# led_driver.net
KiCad netlist of a schematic drawn in EAGLE
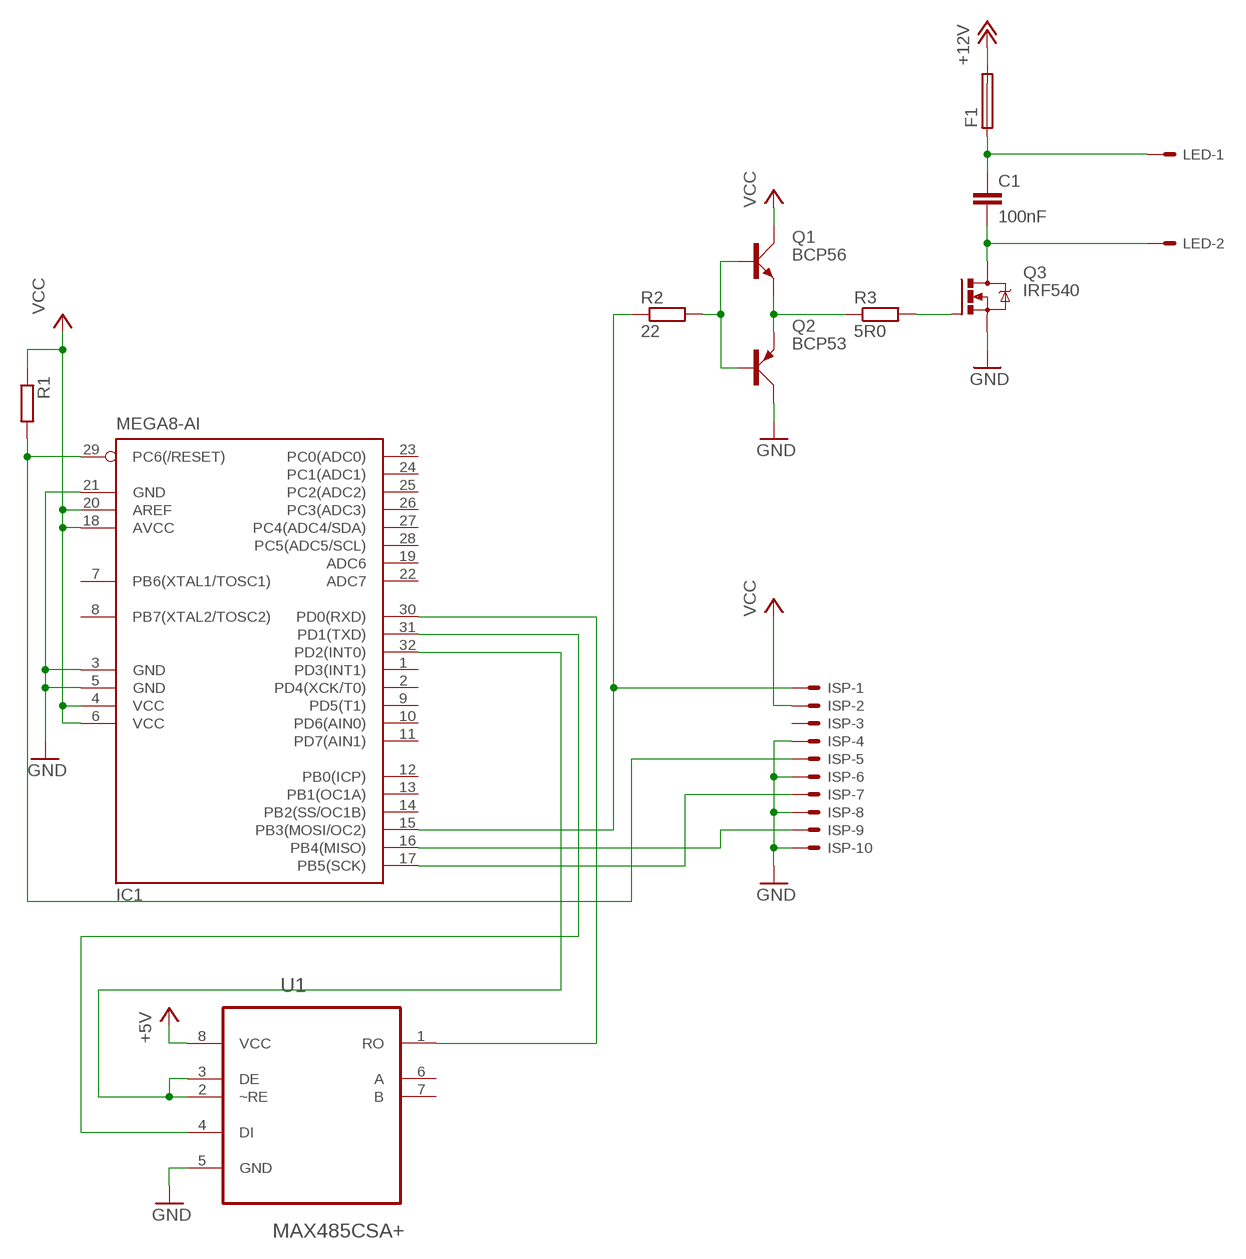
[diagram p0: schematic, sheet 1]

(export (version "E")
  (design (tool "Eeschema 10.0.6"))
  (components
    (comp (ref "C1")
      (value "100nF")
      (footprint "eagle-import:C2.5-3")
      (libsource (lib "eagle-import") (part "C2,5-3"))
    )
    (comp (ref "F1")
      (value "TE5")
      (footprint "eagle-import:TE5")
      (libsource (lib "eagle-import") (part "TE5"))
    )
    (comp (ref "IC1")
      (value "MEGA8-AI")
      (footprint "eagle-import:TQFP32-08")
      (fields (field (name "MPN") "ATMEGA8-16AU"))
      (libsource (lib "eagle-import") (part "MEGA8-AI"))
    )
    (comp (ref "ISP")
      (value "5566-10")
      (footprint "eagle-import:5566-10")
      (libsource (lib "eagle-import") (part "5566-10"))
    )
    (comp (ref "LED")
      (value "5566-10")
      (footprint "eagle-import:5566-10")
      (libsource (lib "eagle-import") (part "5566-10"))
    )
    (comp (ref "Q1")
      (value "BCP56")
      (footprint "eagle-import:SOT54D")
      (libsource (lib "eagle-import") (part "BC639"))
    )
    (comp (ref "Q2")
      (value "BCP53")
      (footprint "eagle-import:SOT54D")
      (libsource (lib "eagle-import") (part "BC640"))
    )
    (comp (ref "Q3")
      (value "IRF540")
      (footprint "eagle-import:TO220BV")
      (libsource (lib "eagle-import") (part "IRF540"))
    )
    (comp (ref "R1")
      (value "R-EU_M1206")
      (footprint "eagle-import:M1206")
      (libsource (lib "eagle-import") (part "R-EU_M1206"))
    )
    (comp (ref "R2")
      (value "22")
      (footprint "eagle-import:R1206")
      (libsource (lib "eagle-import") (part "R-EU_R1206"))
    )
    (comp (ref "R3")
      (value "5R0")
      (footprint "eagle-import:R1206")
      (libsource (lib "eagle-import") (part "R-EU_R1206"))
    )
    (comp (ref "U1")
      (value "MAX485CSA+")
      (footprint "eagle-import:SOIC127P600X175-8N")
      (libsource (lib "eagle-import") (part "MAX485CSA+"))
    )
  )
  (nets
    (net (code "1") (name "+5V") (class "Default")
      (node (ref "U1") (pin "8") (pinfunction "VCC_8") (pintype "power_in"))
    )
    (net (code "2") (name "+12V") (class "Default")
      (node (ref "F1") (pin "2") (pinfunction "2_2") (pintype "passive"))
    )
    (net (code "3") (name "GND") (class "Default")
      (node (ref "IC1") (pin "21") (pinfunction "GND_21") (pintype "power_in"))
      (node (ref "IC1") (pin "3") (pinfunction "GND_3") (pintype "power_in"))
      (node (ref "IC1") (pin "5") (pinfunction "GND_5") (pintype "power_in"))
      (node (ref "ISP") (pin "10") (pinfunction "S_10") (pintype "passive"))
      (node (ref "ISP") (pin "4") (pinfunction "S_4") (pintype "passive"))
      (node (ref "ISP") (pin "6") (pinfunction "S_6") (pintype "passive"))
      (node (ref "ISP") (pin "8") (pinfunction "S_8") (pintype "passive"))
      (node (ref "Q2") (pin "C") (pinfunction "C_C") (pintype "passive"))
      (node (ref "Q3") (pin "S") (pinfunction "S_S") (pintype "passive"))
      (node (ref "U1") (pin "5") (pinfunction "GND_5") (pintype "passive"))
    )
    (net (code "4") (name "Net-(IC1-PB3(MOSI{slash}OC2))") (class "Default")
      (node (ref "IC1") (pin "15") (pinfunction "PB3(MOSI/OC2)_15") (pintype "bidirectional"))
      (node (ref "ISP") (pin "1") (pinfunction "S_1") (pintype "passive"))
      (node (ref "R2") (pin "1") (pinfunction "1_1") (pintype "passive"))
    )
    (net (code "5") (name "Net-(IC1-PB4(MISO))") (class "Default")
      (node (ref "IC1") (pin "16") (pinfunction "PB4(MISO)_16") (pintype "bidirectional"))
      (node (ref "ISP") (pin "9") (pinfunction "S_9") (pintype "passive"))
    )
    (net (code "6") (name "Net-(IC1-PB5(SCK))") (class "Default")
      (node (ref "IC1") (pin "17") (pinfunction "PB5(SCK)_17") (pintype "bidirectional"))
      (node (ref "ISP") (pin "7") (pinfunction "S_7") (pintype "passive"))
    )
    (net (code "7") (name "Net-(IC1-PC6({slash}RESET))") (class "Default")
      (node (ref "IC1") (pin "29") (pinfunction "PC6(/RESET)_29") (pintype "bidirectional"))
      (node (ref "ISP") (pin "5") (pinfunction "S_5") (pintype "passive"))
      (node (ref "R1") (pin "2") (pinfunction "2_2") (pintype "passive"))
    )
    (net (code "8") (name "Net-(IC1-PD0(RXD))") (class "Default")
      (node (ref "IC1") (pin "30") (pinfunction "PD0(RXD)_30") (pintype "bidirectional"))
      (node (ref "U1") (pin "1") (pinfunction "RO_1") (pintype "output"))
    )
    (net (code "9") (name "Net-(IC1-PD1(TXD))") (class "Default")
      (node (ref "IC1") (pin "31") (pinfunction "PD1(TXD)_31") (pintype "bidirectional"))
      (node (ref "U1") (pin "4") (pinfunction "DI_4") (pintype "input"))
    )
    (net (code "10") (name "Net-(IC1-PD2(INT0))") (class "Default")
      (node (ref "IC1") (pin "32") (pinfunction "PD2(INT0)_32") (pintype "bidirectional"))
      (node (ref "U1") (pin "2") (pinfunction "~{RE}_2") (pintype "input"))
      (node (ref "U1") (pin "3") (pinfunction "DE_3") (pintype "input"))
    )
    (net (code "11") (name "Net-(LEDA-S)") (class "Default")
      (node (ref "C1") (pin "1") (pinfunction "1_1") (pintype "passive"))
      (node (ref "F1") (pin "1") (pinfunction "1_1") (pintype "passive"))
      (node (ref "LED") (pin "1") (pinfunction "S_1") (pintype "passive"))
    )
    (net (code "12") (name "Net-(LEDC-S)") (class "Default")
      (node (ref "C1") (pin "2") (pinfunction "2_2") (pintype "passive"))
      (node (ref "LED") (pin "2") (pinfunction "S_2") (pintype "passive"))
      (node (ref "Q3") (pin "D") (pinfunction "D_D") (pintype "passive"))
    )
    (net (code "13") (name "Net-(Q1-PadB)") (class "Default")
      (node (ref "Q1") (pin "B") (pinfunction "B_B") (pintype "passive"))
      (node (ref "Q2") (pin "B") (pinfunction "B_B") (pintype "passive"))
      (node (ref "R2") (pin "2") (pinfunction "2_2") (pintype "passive"))
    )
    (net (code "14") (name "Net-(Q1-PadE)") (class "Default")
      (node (ref "Q1") (pin "E") (pinfunction "E_E") (pintype "passive"))
      (node (ref "Q2") (pin "E") (pinfunction "E_E") (pintype "passive"))
      (node (ref "R3") (pin "1") (pinfunction "1_1") (pintype "passive"))
    )
    (net (code "15") (name "Net-(Q3-PadG)") (class "Default")
      (node (ref "Q3") (pin "G") (pinfunction "G_G") (pintype "passive"))
      (node (ref "R3") (pin "2") (pinfunction "2_2") (pintype "passive"))
    )
    (net (code "16") (name "VCC") (class "Default")
      (node (ref "IC1") (pin "18") (pinfunction "AVCC_18") (pintype "power_in"))
      (node (ref "IC1") (pin "20") (pinfunction "AREF_20") (pintype "passive"))
      (node (ref "IC1") (pin "4") (pinfunction "VCC_4") (pintype "power_in"))
      (node (ref "IC1") (pin "6") (pinfunction "VCC_6") (pintype "power_in"))
      (node (ref "ISP") (pin "2") (pinfunction "S_2") (pintype "passive"))
      (node (ref "Q1") (pin "C") (pinfunction "C_C") (pintype "passive"))
      (node (ref "R1") (pin "1") (pinfunction "1_1") (pintype "passive"))
    )
    (net (code "17") (name "unconnected-(IC1-ADC6-Pad19)") (class "Default")
      (node (ref "IC1") (pin "19") (pinfunction "ADC6_19") (pintype "bidirectional"))
    )
    (net (code "18") (name "unconnected-(IC1-ADC7-Pad22)") (class "Default")
      (node (ref "IC1") (pin "22") (pinfunction "ADC7_22") (pintype "bidirectional"))
    )
    (net (code "19") (name "unconnected-(IC1-PB0(ICP)-Pad12)") (class "Default")
      (node (ref "IC1") (pin "12") (pinfunction "PB0(ICP)_12") (pintype "bidirectional"))
    )
    (net (code "20") (name "unconnected-(IC1-PB1(OC1A)-Pad13)") (class "Default")
      (node (ref "IC1") (pin "13") (pinfunction "PB1(OC1A)_13") (pintype "bidirectional"))
    )
    (net (code "21") (name "unconnected-(IC1-PB2(SS{slash}OC1B)-Pad14)") (class "Default")
      (node (ref "IC1") (pin "14") (pinfunction "PB2(SS/OC1B)_14") (pintype "bidirectional"))
    )
    (net (code "22") (name "unconnected-(IC1-PB6(XTAL1{slash}TOSC1)-Pad7)") (class "Default")
      (node (ref "IC1") (pin "7") (pinfunction "PB6(XTAL1/TOSC1)_7") (pintype "bidirectional"))
    )
    (net (code "23") (name "unconnected-(IC1-PB7(XTAL2{slash}TOSC2)-Pad8)") (class "Default")
      (node (ref "IC1") (pin "8") (pinfunction "PB7(XTAL2/TOSC2)_8") (pintype "bidirectional"))
    )
    (net (code "24") (name "unconnected-(IC1-PC0(ADC0)-Pad23)") (class "Default")
      (node (ref "IC1") (pin "23") (pinfunction "PC0(ADC0)_23") (pintype "bidirectional"))
    )
    (net (code "25") (name "unconnected-(IC1-PC1(ADC1)-Pad24)") (class "Default")
      (node (ref "IC1") (pin "24") (pinfunction "PC1(ADC1)_24") (pintype "bidirectional"))
    )
    (net (code "26") (name "unconnected-(IC1-PC2(ADC2)-Pad25)") (class "Default")
      (node (ref "IC1") (pin "25") (pinfunction "PC2(ADC2)_25") (pintype "bidirectional"))
    )
    (net (code "27") (name "unconnected-(IC1-PC3(ADC3)-Pad26)") (class "Default")
      (node (ref "IC1") (pin "26") (pinfunction "PC3(ADC3)_26") (pintype "bidirectional"))
    )
    (net (code "28") (name "unconnected-(IC1-PC4(ADC4{slash}SDA)-Pad27)") (class "Default")
      (node (ref "IC1") (pin "27") (pinfunction "PC4(ADC4/SDA)_27") (pintype "bidirectional"))
    )
    (net (code "29") (name "unconnected-(IC1-PC5(ADC5{slash}SCL)-Pad28)") (class "Default")
      (node (ref "IC1") (pin "28") (pinfunction "PC5(ADC5/SCL)_28") (pintype "bidirectional"))
    )
    (net (code "30") (name "unconnected-(IC1-PD3(INT1)-Pad1)") (class "Default")
      (node (ref "IC1") (pin "1") (pinfunction "PD3(INT1)_1") (pintype "bidirectional"))
    )
    (net (code "31") (name "unconnected-(IC1-PD4(XCK{slash}T0)-Pad2)") (class "Default")
      (node (ref "IC1") (pin "2") (pinfunction "PD4(XCK/T0)_2") (pintype "bidirectional"))
    )
    (net (code "32") (name "unconnected-(IC1-PD5(T1)-Pad9)") (class "Default")
      (node (ref "IC1") (pin "9") (pinfunction "PD5(T1)_9") (pintype "bidirectional"))
    )
    (net (code "33") (name "unconnected-(IC1-PD6(AIN0)-Pad10)") (class "Default")
      (node (ref "IC1") (pin "10") (pinfunction "PD6(AIN0)_10") (pintype "bidirectional"))
    )
    (net (code "34") (name "unconnected-(IC1-PD7(AIN1)-Pad11)") (class "Default")
      (node (ref "IC1") (pin "11") (pinfunction "PD7(AIN1)_11") (pintype "bidirectional"))
    )
    (net (code "35") (name "unconnected-(ISPD-S-Pad3)") (class "Default")
      (node (ref "ISP") (pin "3") (pinfunction "S_3") (pintype "passive"))
    )
    (net (code "36") (name "unconnected-(U1-A-Pad6)") (class "Default")
      (node (ref "U1") (pin "6") (pinfunction "A_6") (pintype "bidirectional"))
    )
    (net (code "37") (name "unconnected-(U1-B-Pad7)") (class "Default")
      (node (ref "U1") (pin "7") (pinfunction "B_7") (pintype "bidirectional"))
    )
  )
)
